# VHCDI.net
KiCad netlist of a schematic drawn in Altium Designer
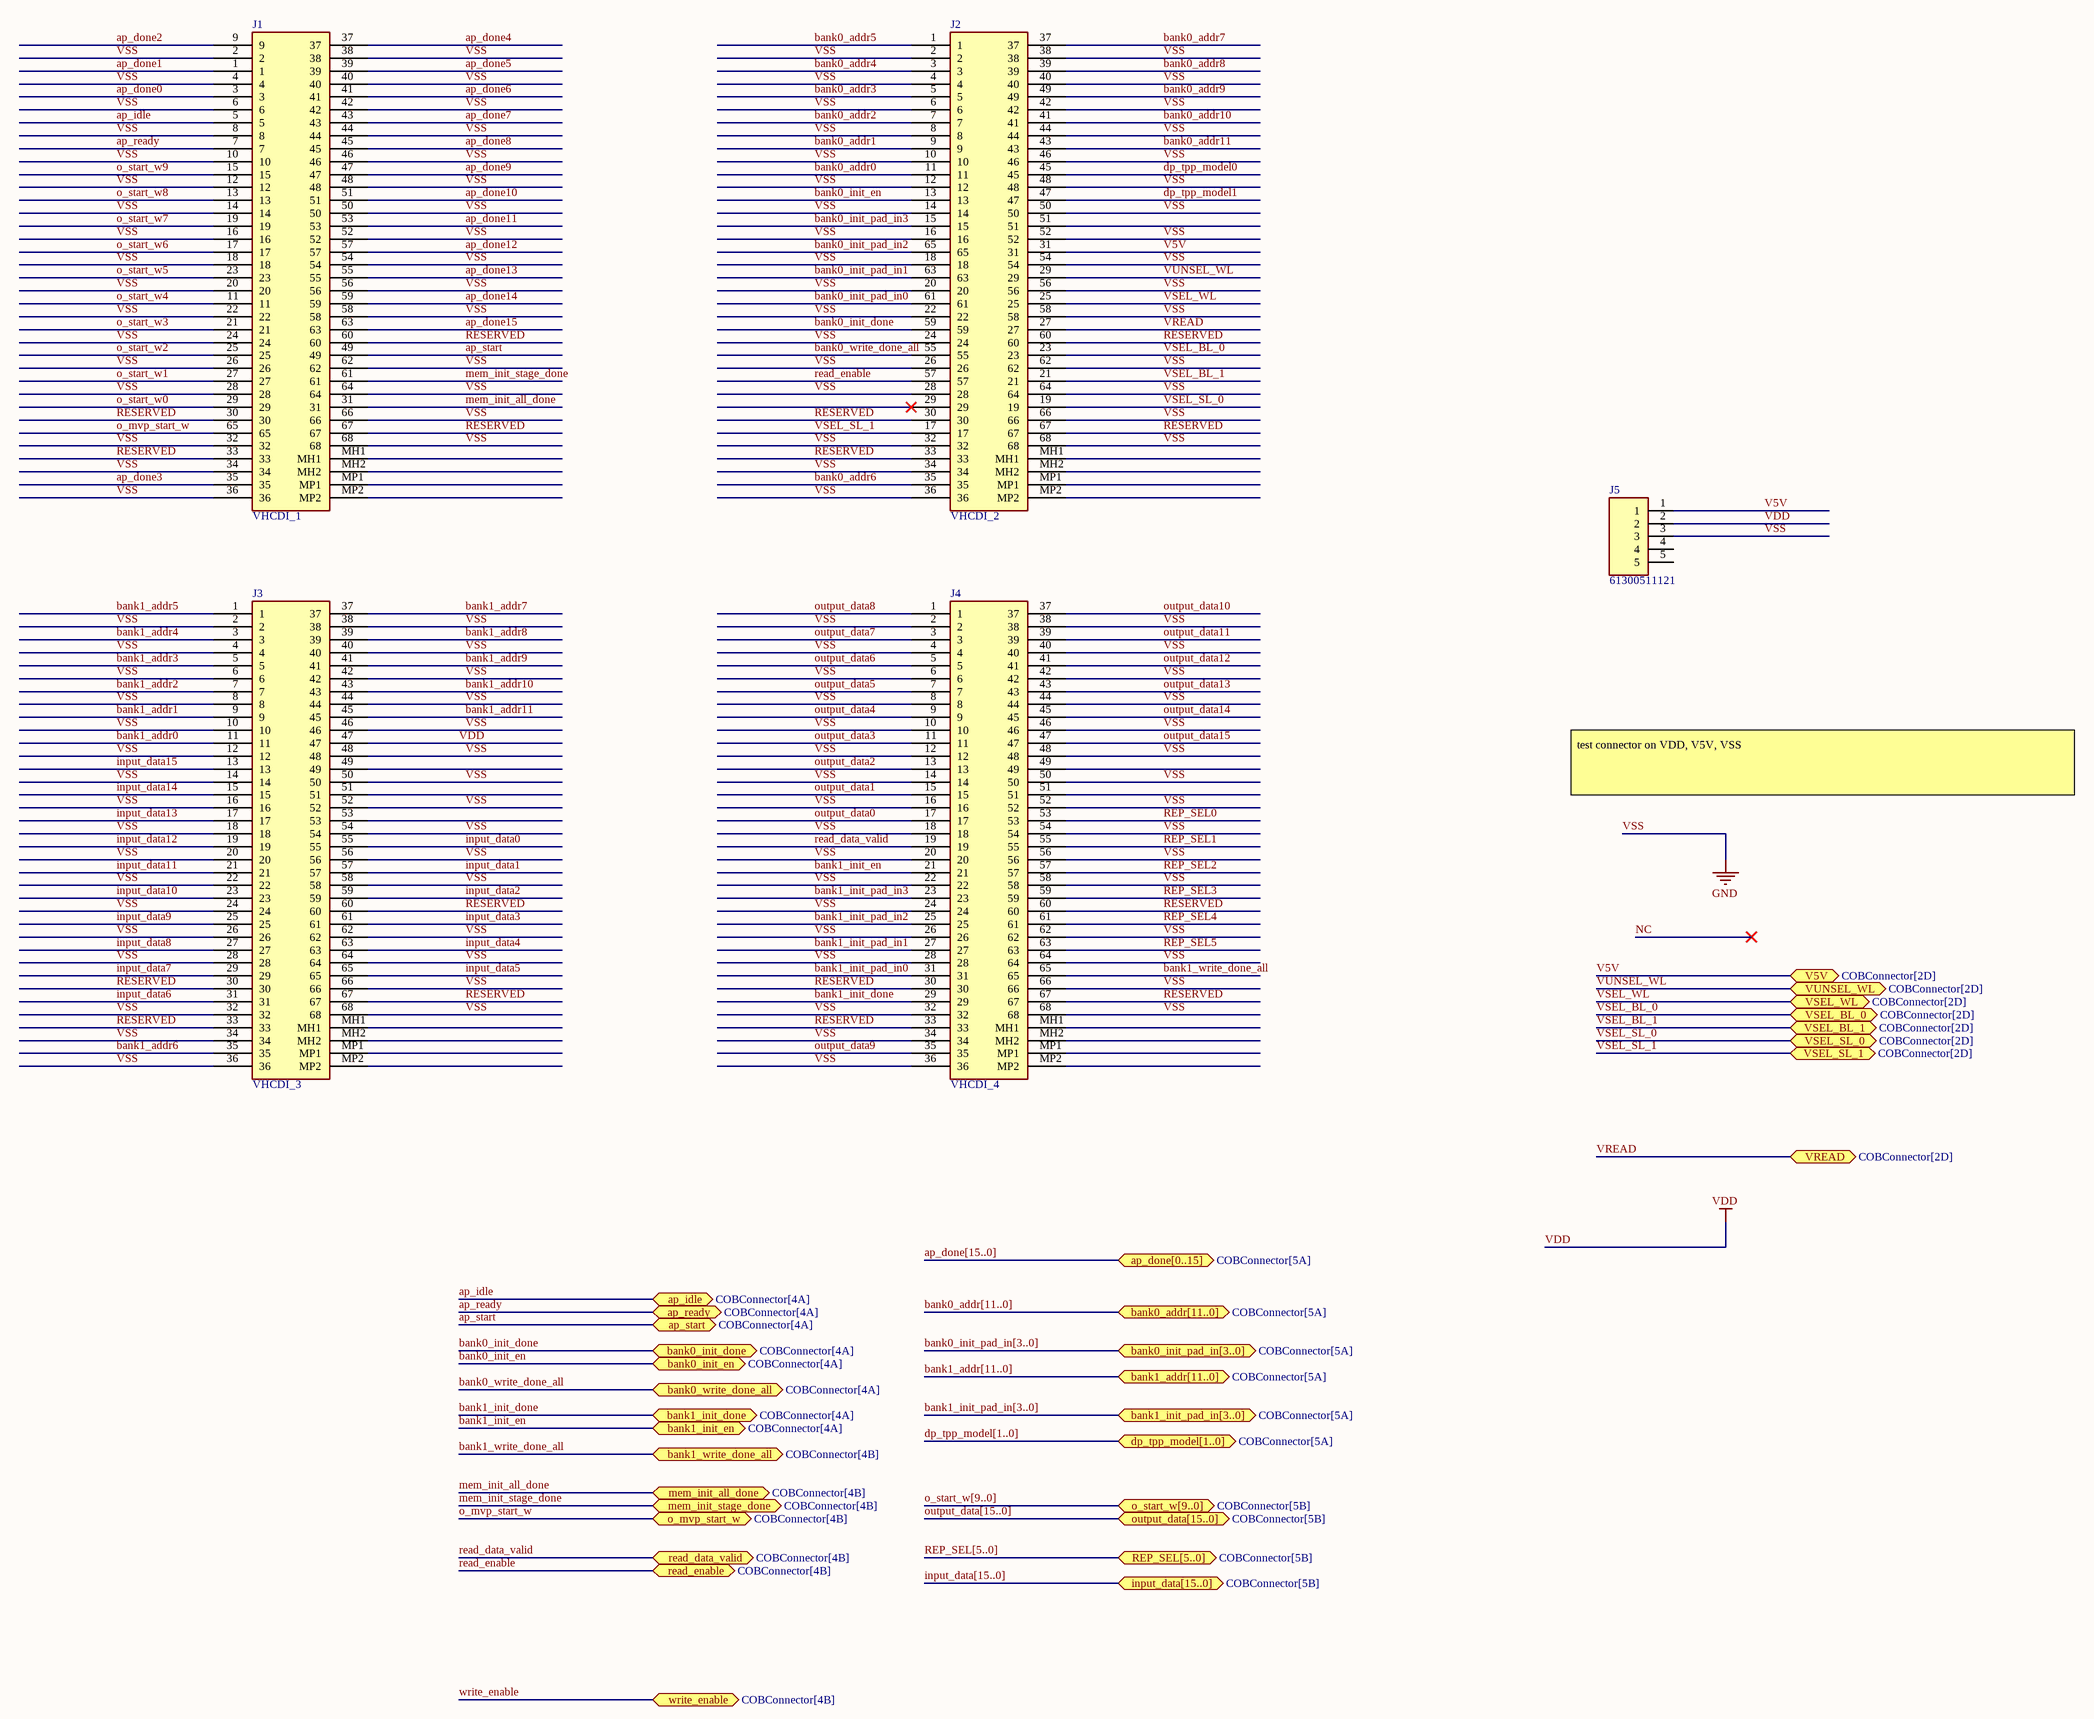
[diagram p0: VHCDI.SchDoc]

(export (version "E")
  (design (tool "Eeschema 10.0.6"))
  (components
    (comp (ref "J1")
      (value "VHCDI_1")
      (footprint "CONN68_HDRA-EC_HON")
      (description "Connector")
      (fields (field (name "MANUFACTURER_PART_NUMBER") "785633-01"))
      (libsource (lib "") (part "785633-01_3"))
    )
    (comp (ref "J2")
      (value "VHCDI_2")
      (footprint "CONN68_HDRA-EC_HON")
      (description "Connector")
      (fields (field (name "MANUFACTURER_PART_NUMBER") "785633-01"))
      (libsource (lib "") (part "785633-01_1"))
    )
    (comp (ref "J3")
      (value "VHCDI_3")
      (footprint "CONN68_HDRA-EC_HON")
      (description "Connector")
      (fields (field (name "MANUFACTURER_PART_NUMBER") "785633-01"))
      (libsource (lib "") (part "785633-01_2"))
    )
    (comp (ref "J4")
      (value "VHCDI_4")
      (footprint "CONN68_HDRA-EC_HON")
      (description "Connector")
      (fields (field (name "MANUFACTURER_PART_NUMBER") "785633-01"))
      (libsource (lib "00-100001-001") (part "785633-01"))
    )
    (comp (ref "J5")
      (value "61300511121")
      (footprint "HDRV5W64P0X254_1X5_1270X254X854P")
      (description "Connector")
      (fields (field (name "MOUSER PART NUMBER") "710-61300511121"))
      (libsource (lib "00-100001-001") (part "61300511121"))
    )
  )
  (nets
    (net (code "2") (name "/REP_SEL0") (class "Default")
      (node (ref "J4") (pin "53") (pinfunction "53_53") (pintype "passive"))
    )
    (net (code "3") (name "/REP_SEL1") (class "Default")
      (node (ref "J4") (pin "55") (pinfunction "55_55") (pintype "passive"))
    )
    (net (code "4") (name "/REP_SEL2") (class "Default")
      (node (ref "J4") (pin "57") (pinfunction "57_57") (pintype "passive"))
    )
    (net (code "5") (name "/REP_SEL3") (class "Default")
      (node (ref "J4") (pin "59") (pinfunction "59_59") (pintype "passive"))
    )
    (net (code "6") (name "/REP_SEL4") (class "Default")
      (node (ref "J4") (pin "61") (pinfunction "61_61") (pintype "passive"))
    )
    (net (code "7") (name "/REP_SEL5") (class "Default")
      (node (ref "J4") (pin "63") (pinfunction "63_63") (pintype "passive"))
    )
    (net (code "9") (name "/RESERVED") (class "Default")
      (node (ref "J1") (pin "30") (pinfunction "30_30") (pintype "passive"))
      (node (ref "J1") (pin "33") (pinfunction "33_33") (pintype "passive"))
      (node (ref "J1") (pin "60") (pinfunction "60_60") (pintype "passive"))
      (node (ref "J1") (pin "67") (pinfunction "67_67") (pintype "passive"))
      (node (ref "J2") (pin "30") (pinfunction "30_30") (pintype "passive"))
      (node (ref "J2") (pin "33") (pinfunction "33_33") (pintype "passive"))
      (node (ref "J2") (pin "60") (pinfunction "60_60") (pintype "passive"))
      (node (ref "J2") (pin "67") (pinfunction "67_67") (pintype "passive"))
      (node (ref "J3") (pin "30") (pinfunction "30_30") (pintype "passive"))
      (node (ref "J3") (pin "33") (pinfunction "33_33") (pintype "passive"))
      (node (ref "J3") (pin "60") (pinfunction "60_60") (pintype "passive"))
      (node (ref "J3") (pin "67") (pinfunction "67_67") (pintype "passive"))
      (node (ref "J4") (pin "30") (pinfunction "30_30") (pintype "passive"))
      (node (ref "J4") (pin "33") (pinfunction "33_33") (pintype "passive"))
      (node (ref "J4") (pin "60") (pinfunction "60_60") (pintype "passive"))
      (node (ref "J4") (pin "67") (pinfunction "67_67") (pintype "passive"))
    )
    (net (code "10") (name "/V5V") (class "Default")
      (node (ref "J2") (pin "31") (pinfunction "31_31") (pintype "passive"))
      (node (ref "J5") (pin "1") (pinfunction "1_1") (pintype "passive"))
    )
    (net (code "11") (name "/VREAD") (class "Default")
      (node (ref "J2") (pin "27") (pinfunction "27_27") (pintype "passive"))
    )
    (net (code "12") (name "/VSEL_BL_0") (class "Default")
      (node (ref "J2") (pin "23") (pinfunction "23_23") (pintype "passive"))
    )
    (net (code "13") (name "/VSEL_BL_1") (class "Default")
      (node (ref "J2") (pin "21") (pinfunction "21_21") (pintype "passive"))
    )
    (net (code "14") (name "/VSEL_SL_0") (class "Default")
      (node (ref "J2") (pin "19") (pinfunction "19_19") (pintype "passive"))
    )
    (net (code "15") (name "/VSEL_SL_1") (class "Default")
      (node (ref "J2") (pin "17") (pinfunction "17_17") (pintype "passive"))
    )
    (net (code "16") (name "/VSEL_WL") (class "Default")
      (node (ref "J2") (pin "25") (pinfunction "25_25") (pintype "passive"))
    )
    (net (code "17") (name "/VUNSEL_WL") (class "Default")
      (node (ref "J2") (pin "29") (pinfunction "29_29") (pintype "passive"))
    )
    (net (code "18") (name "/ap_done0") (class "Default")
      (node (ref "J1") (pin "3") (pinfunction "3_3") (pintype "passive"))
    )
    (net (code "19") (name "/ap_done1") (class "Default")
      (node (ref "J1") (pin "1") (pinfunction "1_1") (pintype "passive"))
    )
    (net (code "20") (name "/ap_done2") (class "Default")
      (node (ref "J1") (pin "9") (pinfunction "9_9") (pintype "passive"))
    )
    (net (code "21") (name "/ap_done3") (class "Default")
      (node (ref "J1") (pin "35") (pinfunction "35_35") (pintype "passive"))
    )
    (net (code "22") (name "/ap_done4") (class "Default")
      (node (ref "J1") (pin "37") (pinfunction "37_37") (pintype "passive"))
    )
    (net (code "23") (name "/ap_done5") (class "Default")
      (node (ref "J1") (pin "39") (pinfunction "39_39") (pintype "passive"))
    )
    (net (code "24") (name "/ap_done6") (class "Default")
      (node (ref "J1") (pin "41") (pinfunction "41_41") (pintype "passive"))
    )
    (net (code "25") (name "/ap_done7") (class "Default")
      (node (ref "J1") (pin "43") (pinfunction "43_43") (pintype "passive"))
    )
    (net (code "26") (name "/ap_done8") (class "Default")
      (node (ref "J1") (pin "45") (pinfunction "45_45") (pintype "passive"))
    )
    (net (code "27") (name "/ap_done9") (class "Default")
      (node (ref "J1") (pin "47") (pinfunction "47_47") (pintype "passive"))
    )
    (net (code "28") (name "/ap_done10") (class "Default")
      (node (ref "J1") (pin "51") (pinfunction "51_51") (pintype "passive"))
    )
    (net (code "29") (name "/ap_done11") (class "Default")
      (node (ref "J1") (pin "53") (pinfunction "53_53") (pintype "passive"))
    )
    (net (code "30") (name "/ap_done12") (class "Default")
      (node (ref "J1") (pin "57") (pinfunction "57_57") (pintype "passive"))
    )
    (net (code "31") (name "/ap_done13") (class "Default")
      (node (ref "J1") (pin "55") (pinfunction "55_55") (pintype "passive"))
    )
    (net (code "32") (name "/ap_done14") (class "Default")
      (node (ref "J1") (pin "59") (pinfunction "59_59") (pintype "passive"))
    )
    (net (code "33") (name "/ap_done15") (class "Default")
      (node (ref "J1") (pin "63") (pinfunction "63_63") (pintype "passive"))
    )
    (net (code "35") (name "/ap_idle") (class "Default")
      (node (ref "J1") (pin "5") (pinfunction "5_5") (pintype "passive"))
    )
    (net (code "36") (name "/ap_ready") (class "Default")
      (node (ref "J1") (pin "7") (pinfunction "7_7") (pintype "passive"))
    )
    (net (code "37") (name "/ap_start") (class "Default")
      (node (ref "J1") (pin "49") (pinfunction "49_49") (pintype "passive"))
    )
    (net (code "38") (name "/bank0_addr0") (class "Default")
      (node (ref "J2") (pin "11") (pinfunction "11_11") (pintype "passive"))
    )
    (net (code "39") (name "/bank0_addr1") (class "Default")
      (node (ref "J2") (pin "9") (pinfunction "9_9") (pintype "passive"))
    )
    (net (code "40") (name "/bank0_addr2") (class "Default")
      (node (ref "J2") (pin "7") (pinfunction "7_7") (pintype "passive"))
    )
    (net (code "41") (name "/bank0_addr3") (class "Default")
      (node (ref "J2") (pin "5") (pinfunction "5_5") (pintype "passive"))
    )
    (net (code "42") (name "/bank0_addr4") (class "Default")
      (node (ref "J2") (pin "3") (pinfunction "3_3") (pintype "passive"))
    )
    (net (code "43") (name "/bank0_addr5") (class "Default")
      (node (ref "J2") (pin "1") (pinfunction "1_1") (pintype "passive"))
    )
    (net (code "44") (name "/bank0_addr6") (class "Default")
      (node (ref "J2") (pin "35") (pinfunction "35_35") (pintype "passive"))
    )
    (net (code "45") (name "/bank0_addr7") (class "Default")
      (node (ref "J2") (pin "37") (pinfunction "37_37") (pintype "passive"))
    )
    (net (code "46") (name "/bank0_addr8") (class "Default")
      (node (ref "J2") (pin "39") (pinfunction "39_39") (pintype "passive"))
    )
    (net (code "47") (name "/bank0_addr9") (class "Default")
      (node (ref "J2") (pin "49") (pinfunction "49_49") (pintype "passive"))
    )
    (net (code "48") (name "/bank0_addr10") (class "Default")
      (node (ref "J2") (pin "41") (pinfunction "41_41") (pintype "passive"))
    )
    (net (code "49") (name "/bank0_addr11") (class "Default")
      (node (ref "J2") (pin "43") (pinfunction "43_43") (pintype "passive"))
    )
    (net (code "51") (name "/bank0_init_done") (class "Default")
      (node (ref "J2") (pin "59") (pinfunction "59_59") (pintype "passive"))
    )
    (net (code "52") (name "/bank0_init_en") (class "Default")
      (node (ref "J2") (pin "13") (pinfunction "13_13") (pintype "passive"))
    )
    (net (code "53") (name "/bank0_init_pad_in0") (class "Default")
      (node (ref "J2") (pin "61") (pinfunction "61_61") (pintype "passive"))
    )
    (net (code "54") (name "/bank0_init_pad_in1") (class "Default")
      (node (ref "J2") (pin "63") (pinfunction "63_63") (pintype "passive"))
    )
    (net (code "55") (name "/bank0_init_pad_in2") (class "Default")
      (node (ref "J2") (pin "65") (pinfunction "65_65") (pintype "passive"))
    )
    (net (code "56") (name "/bank0_init_pad_in3") (class "Default")
      (node (ref "J2") (pin "15") (pinfunction "15_15") (pintype "passive"))
    )
    (net (code "58") (name "/bank0_write_done_all") (class "Default")
      (node (ref "J2") (pin "55") (pinfunction "55_55") (pintype "passive"))
    )
    (net (code "59") (name "/bank1_addr0") (class "Default")
      (node (ref "J3") (pin "11") (pinfunction "11_11") (pintype "passive"))
    )
    (net (code "60") (name "/bank1_addr1") (class "Default")
      (node (ref "J3") (pin "9") (pinfunction "9_9") (pintype "passive"))
    )
    (net (code "61") (name "/bank1_addr2") (class "Default")
      (node (ref "J3") (pin "7") (pinfunction "7_7") (pintype "passive"))
    )
    (net (code "62") (name "/bank1_addr3") (class "Default")
      (node (ref "J3") (pin "5") (pinfunction "5_5") (pintype "passive"))
    )
    (net (code "63") (name "/bank1_addr4") (class "Default")
      (node (ref "J3") (pin "3") (pinfunction "3_3") (pintype "passive"))
    )
    (net (code "64") (name "/bank1_addr5") (class "Default")
      (node (ref "J3") (pin "1") (pinfunction "1_1") (pintype "passive"))
    )
    (net (code "65") (name "/bank1_addr6") (class "Default")
      (node (ref "J3") (pin "35") (pinfunction "35_35") (pintype "passive"))
    )
    (net (code "66") (name "/bank1_addr7") (class "Default")
      (node (ref "J3") (pin "37") (pinfunction "37_37") (pintype "passive"))
    )
    (net (code "67") (name "/bank1_addr8") (class "Default")
      (node (ref "J3") (pin "39") (pinfunction "39_39") (pintype "passive"))
    )
    (net (code "68") (name "/bank1_addr9") (class "Default")
      (node (ref "J3") (pin "41") (pinfunction "41_41") (pintype "passive"))
    )
    (net (code "69") (name "/bank1_addr10") (class "Default")
      (node (ref "J3") (pin "43") (pinfunction "43_43") (pintype "passive"))
    )
    (net (code "70") (name "/bank1_addr11") (class "Default")
      (node (ref "J3") (pin "45") (pinfunction "45_45") (pintype "passive"))
    )
    (net (code "72") (name "/bank1_init_done") (class "Default")
      (node (ref "J4") (pin "29") (pinfunction "29_29") (pintype "passive"))
    )
    (net (code "73") (name "/bank1_init_en") (class "Default")
      (node (ref "J4") (pin "21") (pinfunction "21_21") (pintype "passive"))
    )
    (net (code "74") (name "/bank1_init_pad_in0") (class "Default")
      (node (ref "J4") (pin "31") (pinfunction "31_31") (pintype "passive"))
    )
    (net (code "75") (name "/bank1_init_pad_in1") (class "Default")
      (node (ref "J4") (pin "27") (pinfunction "27_27") (pintype "passive"))
    )
    (net (code "76") (name "/bank1_init_pad_in2") (class "Default")
      (node (ref "J4") (pin "25") (pinfunction "25_25") (pintype "passive"))
    )
    (net (code "77") (name "/bank1_init_pad_in3") (class "Default")
      (node (ref "J4") (pin "23") (pinfunction "23_23") (pintype "passive"))
    )
    (net (code "79") (name "/bank1_write_done_all") (class "Default")
      (node (ref "J4") (pin "65") (pinfunction "65_65") (pintype "passive"))
    )
    (net (code "80") (name "/dp_tpp_model0") (class "Default")
      (node (ref "J2") (pin "45") (pinfunction "45_45") (pintype "passive"))
    )
    (net (code "81") (name "/dp_tpp_model1") (class "Default")
      (node (ref "J2") (pin "47") (pinfunction "47_47") (pintype "passive"))
    )
    (net (code "83") (name "/input_data0") (class "Default")
      (node (ref "J3") (pin "55") (pinfunction "55_55") (pintype "passive"))
    )
    (net (code "84") (name "/input_data1") (class "Default")
      (node (ref "J3") (pin "57") (pinfunction "57_57") (pintype "passive"))
    )
    (net (code "85") (name "/input_data2") (class "Default")
      (node (ref "J3") (pin "59") (pinfunction "59_59") (pintype "passive"))
    )
    (net (code "86") (name "/input_data3") (class "Default")
      (node (ref "J3") (pin "61") (pinfunction "61_61") (pintype "passive"))
    )
    (net (code "87") (name "/input_data4") (class "Default")
      (node (ref "J3") (pin "63") (pinfunction "63_63") (pintype "passive"))
    )
    (net (code "88") (name "/input_data5") (class "Default")
      (node (ref "J3") (pin "65") (pinfunction "65_65") (pintype "passive"))
    )
    (net (code "89") (name "/input_data6") (class "Default")
      (node (ref "J3") (pin "31") (pinfunction "31_31") (pintype "passive"))
    )
    (net (code "90") (name "/input_data7") (class "Default")
      (node (ref "J3") (pin "29") (pinfunction "29_29") (pintype "passive"))
    )
    (net (code "91") (name "/input_data8") (class "Default")
      (node (ref "J3") (pin "27") (pinfunction "27_27") (pintype "passive"))
    )
    (net (code "92") (name "/input_data9") (class "Default")
      (node (ref "J3") (pin "25") (pinfunction "25_25") (pintype "passive"))
    )
    (net (code "93") (name "/input_data10") (class "Default")
      (node (ref "J3") (pin "23") (pinfunction "23_23") (pintype "passive"))
    )
    (net (code "94") (name "/input_data11") (class "Default")
      (node (ref "J3") (pin "21") (pinfunction "21_21") (pintype "passive"))
    )
    (net (code "95") (name "/input_data12") (class "Default")
      (node (ref "J3") (pin "19") (pinfunction "19_19") (pintype "passive"))
    )
    (net (code "96") (name "/input_data13") (class "Default")
      (node (ref "J3") (pin "17") (pinfunction "17_17") (pintype "passive"))
    )
    (net (code "97") (name "/input_data14") (class "Default")
      (node (ref "J3") (pin "15") (pinfunction "15_15") (pintype "passive"))
    )
    (net (code "98") (name "/input_data15") (class "Default")
      (node (ref "J3") (pin "13") (pinfunction "13_13") (pintype "passive"))
    )
    (net (code "100") (name "/mem_init_all_done") (class "Default")
      (node (ref "J1") (pin "31") (pinfunction "31_31") (pintype "passive"))
    )
    (net (code "101") (name "/mem_init_stage_done") (class "Default")
      (node (ref "J1") (pin "61") (pinfunction "61_61") (pintype "passive"))
    )
    (net (code "102") (name "/o_mvp_start_w") (class "Default")
      (node (ref "J1") (pin "65") (pinfunction "65_65") (pintype "passive"))
    )
    (net (code "103") (name "/o_start_w0") (class "Default")
      (node (ref "J1") (pin "29") (pinfunction "29_29") (pintype "passive"))
    )
    (net (code "104") (name "/o_start_w1") (class "Default")
      (node (ref "J1") (pin "27") (pinfunction "27_27") (pintype "passive"))
    )
    (net (code "105") (name "/o_start_w2") (class "Default")
      (node (ref "J1") (pin "25") (pinfunction "25_25") (pintype "passive"))
    )
    (net (code "106") (name "/o_start_w3") (class "Default")
      (node (ref "J1") (pin "21") (pinfunction "21_21") (pintype "passive"))
    )
    (net (code "107") (name "/o_start_w4") (class "Default")
      (node (ref "J1") (pin "11") (pinfunction "11_11") (pintype "passive"))
    )
    (net (code "108") (name "/o_start_w5") (class "Default")
      (node (ref "J1") (pin "23") (pinfunction "23_23") (pintype "passive"))
    )
    (net (code "109") (name "/o_start_w6") (class "Default")
      (node (ref "J1") (pin "17") (pinfunction "17_17") (pintype "passive"))
    )
    (net (code "110") (name "/o_start_w7") (class "Default")
      (node (ref "J1") (pin "19") (pinfunction "19_19") (pintype "passive"))
    )
    (net (code "111") (name "/o_start_w8") (class "Default")
      (node (ref "J1") (pin "13") (pinfunction "13_13") (pintype "passive"))
    )
    (net (code "112") (name "/o_start_w9") (class "Default")
      (node (ref "J1") (pin "15") (pinfunction "15_15") (pintype "passive"))
    )
    (net (code "114") (name "/output_data0") (class "Default")
      (node (ref "J4") (pin "17") (pinfunction "17_17") (pintype "passive"))
    )
    (net (code "115") (name "/output_data1") (class "Default")
      (node (ref "J4") (pin "15") (pinfunction "15_15") (pintype "passive"))
    )
    (net (code "116") (name "/output_data2") (class "Default")
      (node (ref "J4") (pin "13") (pinfunction "13_13") (pintype "passive"))
    )
    (net (code "117") (name "/output_data3") (class "Default")
      (node (ref "J4") (pin "11") (pinfunction "11_11") (pintype "passive"))
    )
    (net (code "118") (name "/output_data4") (class "Default")
      (node (ref "J4") (pin "9") (pinfunction "9_9") (pintype "passive"))
    )
    (net (code "119") (name "/output_data5") (class "Default")
      (node (ref "J4") (pin "7") (pinfunction "7_7") (pintype "passive"))
    )
    (net (code "120") (name "/output_data6") (class "Default")
      (node (ref "J4") (pin "5") (pinfunction "5_5") (pintype "passive"))
    )
    (net (code "121") (name "/output_data7") (class "Default")
      (node (ref "J4") (pin "3") (pinfunction "3_3") (pintype "passive"))
    )
    (net (code "122") (name "/output_data8") (class "Default")
      (node (ref "J4") (pin "1") (pinfunction "1_1") (pintype "passive"))
    )
    (net (code "123") (name "/output_data9") (class "Default")
      (node (ref "J4") (pin "35") (pinfunction "35_35") (pintype "passive"))
    )
    (net (code "124") (name "/output_data10") (class "Default")
      (node (ref "J4") (pin "37") (pinfunction "37_37") (pintype "passive"))
    )
    (net (code "125") (name "/output_data11") (class "Default")
      (node (ref "J4") (pin "39") (pinfunction "39_39") (pintype "passive"))
    )
    (net (code "126") (name "/output_data12") (class "Default")
      (node (ref "J4") (pin "41") (pinfunction "41_41") (pintype "passive"))
    )
    (net (code "127") (name "/output_data13") (class "Default")
      (node (ref "J4") (pin "43") (pinfunction "43_43") (pintype "passive"))
    )
    (net (code "128") (name "/output_data14") (class "Default")
      (node (ref "J4") (pin "45") (pinfunction "45_45") (pintype "passive"))
    )
    (net (code "129") (name "/output_data15") (class "Default")
      (node (ref "J4") (pin "47") (pinfunction "47_47") (pintype "passive"))
    )
    (net (code "131") (name "/read_data_valid") (class "Default")
      (node (ref "J4") (pin "19") (pinfunction "19_19") (pintype "passive"))
    )
    (net (code "132") (name "/read_enable") (class "Default")
      (node (ref "J2") (pin "57") (pinfunction "57_57") (pintype "passive"))
    )
    (net (code "134") (name "GND") (class "Default")
      (node (ref "J1") (pin "10") (pinfunction "10_10") (pintype "passive"))
      (node (ref "J1") (pin "12") (pinfunction "12_12") (pintype "passive"))
      (node (ref "J1") (pin "14") (pinfunction "14_14") (pintype "passive"))
      (node (ref "J1") (pin "16") (pinfunction "16_16") (pintype "passive"))
      (node (ref "J1") (pin "18") (pinfunction "18_18") (pintype "passive"))
      (node (ref "J1") (pin "2") (pinfunction "2_2") (pintype "passive"))
      (node (ref "J1") (pin "20") (pinfunction "20_20") (pintype "passive"))
      (node (ref "J1") (pin "22") (pinfunction "22_22") (pintype "passive"))
      (node (ref "J1") (pin "24") (pinfunction "24_24") (pintype "passive"))
      (node (ref "J1") (pin "26") (pinfunction "26_26") (pintype "passive"))
      (node (ref "J1") (pin "28") (pinfunction "28_28") (pintype "passive"))
      (node (ref "J1") (pin "32") (pinfunction "32_32") (pintype "passive"))
      (node (ref "J1") (pin "34") (pinfunction "34_34") (pintype "passive"))
      (node (ref "J1") (pin "36") (pinfunction "36_36") (pintype "passive"))
      (node (ref "J1") (pin "38") (pinfunction "38_38") (pintype "passive"))
      (node (ref "J1") (pin "4") (pinfunction "4_4") (pintype "passive"))
      (node (ref "J1") (pin "40") (pinfunction "40_40") (pintype "passive"))
      (node (ref "J1") (pin "42") (pinfunction "42_42") (pintype "passive"))
      (node (ref "J1") (pin "44") (pinfunction "44_44") (pintype "passive"))
      (node (ref "J1") (pin "46") (pinfunction "46_46") (pintype "passive"))
      (node (ref "J1") (pin "48") (pinfunction "48_48") (pintype "passive"))
      (node (ref "J1") (pin "50") (pinfunction "50_50") (pintype "passive"))
      (node (ref "J1") (pin "52") (pinfunction "52_52") (pintype "passive"))
      (node (ref "J1") (pin "54") (pinfunction "54_54") (pintype "passive"))
      (node (ref "J1") (pin "56") (pinfunction "56_56") (pintype "passive"))
      (node (ref "J1") (pin "58") (pinfunction "58_58") (pintype "passive"))
      (node (ref "J1") (pin "6") (pinfunction "6_6") (pintype "passive"))
      (node (ref "J1") (pin "62") (pinfunction "62_62") (pintype "passive"))
      (node (ref "J1") (pin "64") (pinfunction "64_64") (pintype "passive"))
      (node (ref "J1") (pin "66") (pinfunction "66_66") (pintype "passive"))
      (node (ref "J1") (pin "68") (pinfunction "68_68") (pintype "passive"))
      (node (ref "J1") (pin "8") (pinfunction "8_8") (pintype "passive"))
      (node (ref "J2") (pin "10") (pinfunction "10_10") (pintype "passive"))
      (node (ref "J2") (pin "12") (pinfunction "12_12") (pintype "passive"))
      (node (ref "J2") (pin "14") (pinfunction "14_14") (pintype "passive"))
      (node (ref "J2") (pin "16") (pinfunction "16_16") (pintype "passive"))
      (node (ref "J2") (pin "18") (pinfunction "18_18") (pintype "passive"))
      (node (ref "J2") (pin "2") (pinfunction "2_2") (pintype "passive"))
      (node (ref "J2") (pin "20") (pinfunction "20_20") (pintype "passive"))
      (node (ref "J2") (pin "22") (pinfunction "22_22") (pintype "passive"))
      (node (ref "J2") (pin "24") (pinfunction "24_24") (pintype "passive"))
      (node (ref "J2") (pin "26") (pinfunction "26_26") (pintype "passive"))
      (node (ref "J2") (pin "28") (pinfunction "28_28") (pintype "passive"))
      (node (ref "J2") (pin "32") (pinfunction "32_32") (pintype "passive"))
      (node (ref "J2") (pin "34") (pinfunction "34_34") (pintype "passive"))
      (node (ref "J2") (pin "36") (pinfunction "36_36") (pintype "passive"))
      (node (ref "J2") (pin "38") (pinfunction "38_38") (pintype "passive"))
      (node (ref "J2") (pin "4") (pinfunction "4_4") (pintype "passive"))
      (node (ref "J2") (pin "40") (pinfunction "40_40") (pintype "passive"))
      (node (ref "J2") (pin "42") (pinfunction "42_42") (pintype "passive"))
      (node (ref "J2") (pin "44") (pinfunction "44_44") (pintype "passive"))
      (node (ref "J2") (pin "46") (pinfunction "46_46") (pintype "passive"))
      (node (ref "J2") (pin "48") (pinfunction "48_48") (pintype "passive"))
      (node (ref "J2") (pin "50") (pinfunction "50_50") (pintype "passive"))
      (node (ref "J2") (pin "52") (pinfunction "52_52") (pintype "passive"))
      (node (ref "J2") (pin "54") (pinfunction "54_54") (pintype "passive"))
      (node (ref "J2") (pin "56") (pinfunction "56_56") (pintype "passive"))
      (node (ref "J2") (pin "58") (pinfunction "58_58") (pintype "passive"))
      (node (ref "J2") (pin "6") (pinfunction "6_6") (pintype "passive"))
      (node (ref "J2") (pin "62") (pinfunction "62_62") (pintype "passive"))
      (node (ref "J2") (pin "64") (pinfunction "64_64") (pintype "passive"))
      (node (ref "J2") (pin "66") (pinfunction "66_66") (pintype "passive"))
      (node (ref "J2") (pin "68") (pinfunction "68_68") (pintype "passive"))
      (node (ref "J2") (pin "8") (pinfunction "8_8") (pintype "passive"))
      (node (ref "J3") (pin "10") (pinfunction "10_10") (pintype "passive"))
      (node (ref "J3") (pin "12") (pinfunction "12_12") (pintype "passive"))
      (node (ref "J3") (pin "14") (pinfunction "14_14") (pintype "passive"))
      (node (ref "J3") (pin "16") (pinfunction "16_16") (pintype "passive"))
      (node (ref "J3") (pin "18") (pinfunction "18_18") (pintype "passive"))
      (node (ref "J3") (pin "2") (pinfunction "2_2") (pintype "passive"))
      (node (ref "J3") (pin "20") (pinfunction "20_20") (pintype "passive"))
      (node (ref "J3") (pin "22") (pinfunction "22_22") (pintype "passive"))
      (node (ref "J3") (pin "24") (pinfunction "24_24") (pintype "passive"))
      (node (ref "J3") (pin "26") (pinfunction "26_26") (pintype "passive"))
      (node (ref "J3") (pin "28") (pinfunction "28_28") (pintype "passive"))
      (node (ref "J3") (pin "32") (pinfunction "32_32") (pintype "passive"))
      (node (ref "J3") (pin "34") (pinfunction "34_34") (pintype "passive"))
      (node (ref "J3") (pin "36") (pinfunction "36_36") (pintype "passive"))
      (node (ref "J3") (pin "38") (pinfunction "38_38") (pintype "passive"))
      (node (ref "J3") (pin "4") (pinfunction "4_4") (pintype "passive"))
      (node (ref "J3") (pin "40") (pinfunction "40_40") (pintype "passive"))
      (node (ref "J3") (pin "42") (pinfunction "42_42") (pintype "passive"))
      (node (ref "J3") (pin "44") (pinfunction "44_44") (pintype "passive"))
      (node (ref "J3") (pin "46") (pinfunction "46_46") (pintype "passive"))
      (node (ref "J3") (pin "48") (pinfunction "48_48") (pintype "passive"))
      (node (ref "J3") (pin "50") (pinfunction "50_50") (pintype "passive"))
      (node (ref "J3") (pin "52") (pinfunction "52_52") (pintype "passive"))
      (node (ref "J3") (pin "54") (pinfunction "54_54") (pintype "passive"))
      (node (ref "J3") (pin "56") (pinfunction "56_56") (pintype "passive"))
      (node (ref "J3") (pin "58") (pinfunction "58_58") (pintype "passive"))
      (node (ref "J3") (pin "6") (pinfunction "6_6") (pintype "passive"))
      (node (ref "J3") (pin "62") (pinfunction "62_62") (pintype "passive"))
      (node (ref "J3") (pin "64") (pinfunction "64_64") (pintype "passive"))
      (node (ref "J3") (pin "66") (pinfunction "66_66") (pintype "passive"))
      (node (ref "J3") (pin "68") (pinfunction "68_68") (pintype "passive"))
      (node (ref "J3") (pin "8") (pinfunction "8_8") (pintype "passive"))
      (node (ref "J4") (pin "10") (pinfunction "10_10") (pintype "passive"))
      (node (ref "J4") (pin "12") (pinfunction "12_12") (pintype "passive"))
      (node (ref "J4") (pin "14") (pinfunction "14_14") (pintype "passive"))
      (node (ref "J4") (pin "16") (pinfunction "16_16") (pintype "passive"))
      (node (ref "J4") (pin "18") (pinfunction "18_18") (pintype "passive"))
      (node (ref "J4") (pin "2") (pinfunction "2_2") (pintype "passive"))
      (node (ref "J4") (pin "20") (pinfunction "20_20") (pintype "passive"))
      (node (ref "J4") (pin "22") (pinfunction "22_22") (pintype "passive"))
      (node (ref "J4") (pin "24") (pinfunction "24_24") (pintype "passive"))
      (node (ref "J4") (pin "26") (pinfunction "26_26") (pintype "passive"))
      (node (ref "J4") (pin "28") (pinfunction "28_28") (pintype "passive"))
      (node (ref "J4") (pin "32") (pinfunction "32_32") (pintype "passive"))
      (node (ref "J4") (pin "34") (pinfunction "34_34") (pintype "passive"))
      (node (ref "J4") (pin "36") (pinfunction "36_36") (pintype "passive"))
      (node (ref "J4") (pin "38") (pinfunction "38_38") (pintype "passive"))
      (node (ref "J4") (pin "4") (pinfunction "4_4") (pintype "passive"))
      (node (ref "J4") (pin "40") (pinfunction "40_40") (pintype "passive"))
      (node (ref "J4") (pin "42") (pinfunction "42_42") (pintype "passive"))
      (node (ref "J4") (pin "44") (pinfunction "44_44") (pintype "passive"))
      (node (ref "J4") (pin "46") (pinfunction "46_46") (pintype "passive"))
      (node (ref "J4") (pin "48") (pinfunction "48_48") (pintype "passive"))
      (node (ref "J4") (pin "50") (pinfunction "50_50") (pintype "passive"))
      (node (ref "J4") (pin "52") (pinfunction "52_52") (pintype "passive"))
      (node (ref "J4") (pin "54") (pinfunction "54_54") (pintype "passive"))
      (node (ref "J4") (pin "56") (pinfunction "56_56") (pintype "passive"))
      (node (ref "J4") (pin "58") (pinfunction "58_58") (pintype "passive"))
      (node (ref "J4") (pin "6") (pinfunction "6_6") (pintype "passive"))
      (node (ref "J4") (pin "62") (pinfunction "62_62") (pintype "passive"))
      (node (ref "J4") (pin "64") (pinfunction "64_64") (pintype "passive"))
      (node (ref "J4") (pin "66") (pinfunction "66_66") (pintype "passive"))
      (node (ref "J4") (pin "68") (pinfunction "68_68") (pintype "passive"))
      (node (ref "J4") (pin "8") (pinfunction "8_8") (pintype "passive"))
      (node (ref "J5") (pin "3") (pinfunction "3_3") (pintype "passive"))
    )
    (net (code "135") (name "VDD") (class "Default")
      (node (ref "J3") (pin "47") (pinfunction "47_47") (pintype "passive"))
      (node (ref "J5") (pin "2") (pinfunction "2_2") (pintype "passive"))
    )
    (net (code "136") (name "unconnected-(J1-PadMH1)") (class "Default")
      (node (ref "J1") (pin "MH1") (pinfunction "MH1_MH1") (pintype "passive"))
    )
    (net (code "137") (name "unconnected-(J1-PadMH2)") (class "Default")
      (node (ref "J1") (pin "MH2") (pinfunction "MH2_MH2") (pintype "passive"))
    )
    (net (code "138") (name "unconnected-(J1-PadMP1)") (class "Default")
      (node (ref "J1") (pin "MP1") (pinfunction "MP1_MP1") (pintype "passive"))
    )
    (net (code "139") (name "unconnected-(J1-PadMP2)") (class "Default")
      (node (ref "J1") (pin "MP2") (pinfunction "MP2_MP2") (pintype "passive"))
    )
    (net (code "140") (name "unconnected-(J2-Pad29)") (class "Default")
      (node (ref "J2") (pin "29") (pinfunction "29_29") (pintype "passive+no_connect"))
    )
    (net (code "141") (name "unconnected-(J2-Pad51)") (class "Default")
      (node (ref "J2") (pin "51") (pinfunction "51_51") (pintype "passive"))
    )
    (net (code "142") (name "unconnected-(J2-PadMH1)") (class "Default")
      (node (ref "J2") (pin "MH1") (pinfunction "MH1_MH1") (pintype "passive"))
    )
    (net (code "143") (name "unconnected-(J2-PadMH2)") (class "Default")
      (node (ref "J2") (pin "MH2") (pinfunction "MH2_MH2") (pintype "passive"))
    )
    (net (code "144") (name "unconnected-(J2-PadMP1)") (class "Default")
      (node (ref "J2") (pin "MP1") (pinfunction "MP1_MP1") (pintype "passive"))
    )
    (net (code "145") (name "unconnected-(J2-PadMP2)") (class "Default")
      (node (ref "J2") (pin "MP2") (pinfunction "MP2_MP2") (pintype "passive"))
    )
    (net (code "146") (name "unconnected-(J3-Pad49)") (class "Default")
      (node (ref "J3") (pin "49") (pinfunction "49_49") (pintype "passive"))
    )
    (net (code "147") (name "unconnected-(J3-Pad51)") (class "Default")
      (node (ref "J3") (pin "51") (pinfunction "51_51") (pintype "passive"))
    )
    (net (code "148") (name "unconnected-(J3-Pad53)") (class "Default")
      (node (ref "J3") (pin "53") (pinfunction "53_53") (pintype "passive"))
    )
    (net (code "149") (name "unconnected-(J3-PadMH1)") (class "Default")
      (node (ref "J3") (pin "MH1") (pinfunction "MH1_MH1") (pintype "passive"))
    )
    (net (code "150") (name "unconnected-(J3-PadMH2)") (class "Default")
      (node (ref "J3") (pin "MH2") (pinfunction "MH2_MH2") (pintype "passive"))
    )
    (net (code "151") (name "unconnected-(J3-PadMP1)") (class "Default")
      (node (ref "J3") (pin "MP1") (pinfunction "MP1_MP1") (pintype "passive"))
    )
    (net (code "152") (name "unconnected-(J3-PadMP2)") (class "Default")
      (node (ref "J3") (pin "MP2") (pinfunction "MP2_MP2") (pintype "passive"))
    )
    (net (code "153") (name "unconnected-(J4-Pad49)") (class "Default")
      (node (ref "J4") (pin "49") (pinfunction "49_49") (pintype "passive"))
    )
    (net (code "154") (name "unconnected-(J4-Pad51)") (class "Default")
      (node (ref "J4") (pin "51") (pinfunction "51_51") (pintype "passive"))
    )
    (net (code "155") (name "unconnected-(J4-PadMH1)") (class "Default")
      (node (ref "J4") (pin "MH1") (pinfunction "MH1_MH1") (pintype "passive"))
    )
    (net (code "156") (name "unconnected-(J4-PadMH2)") (class "Default")
      (node (ref "J4") (pin "MH2") (pinfunction "MH2_MH2") (pintype "passive"))
    )
    (net (code "157") (name "unconnected-(J4-PadMP1)") (class "Default")
      (node (ref "J4") (pin "MP1") (pinfunction "MP1_MP1") (pintype "passive"))
    )
    (net (code "158") (name "unconnected-(J4-PadMP2)") (class "Default")
      (node (ref "J4") (pin "MP2") (pinfunction "MP2_MP2") (pintype "passive"))
    )
    (net (code "159") (name "unconnected-(J5-Pad4)") (class "Default")
      (node (ref "J5") (pin "4") (pinfunction "4_4") (pintype "passive"))
    )
    (net (code "160") (name "unconnected-(J5-Pad5)") (class "Default")
      (node (ref "J5") (pin "5") (pinfunction "5_5") (pintype "passive"))
    )
  )
)
